# FPGA_DDR3_IO.net
KiCad netlist of a schematic drawn in Altium Designer
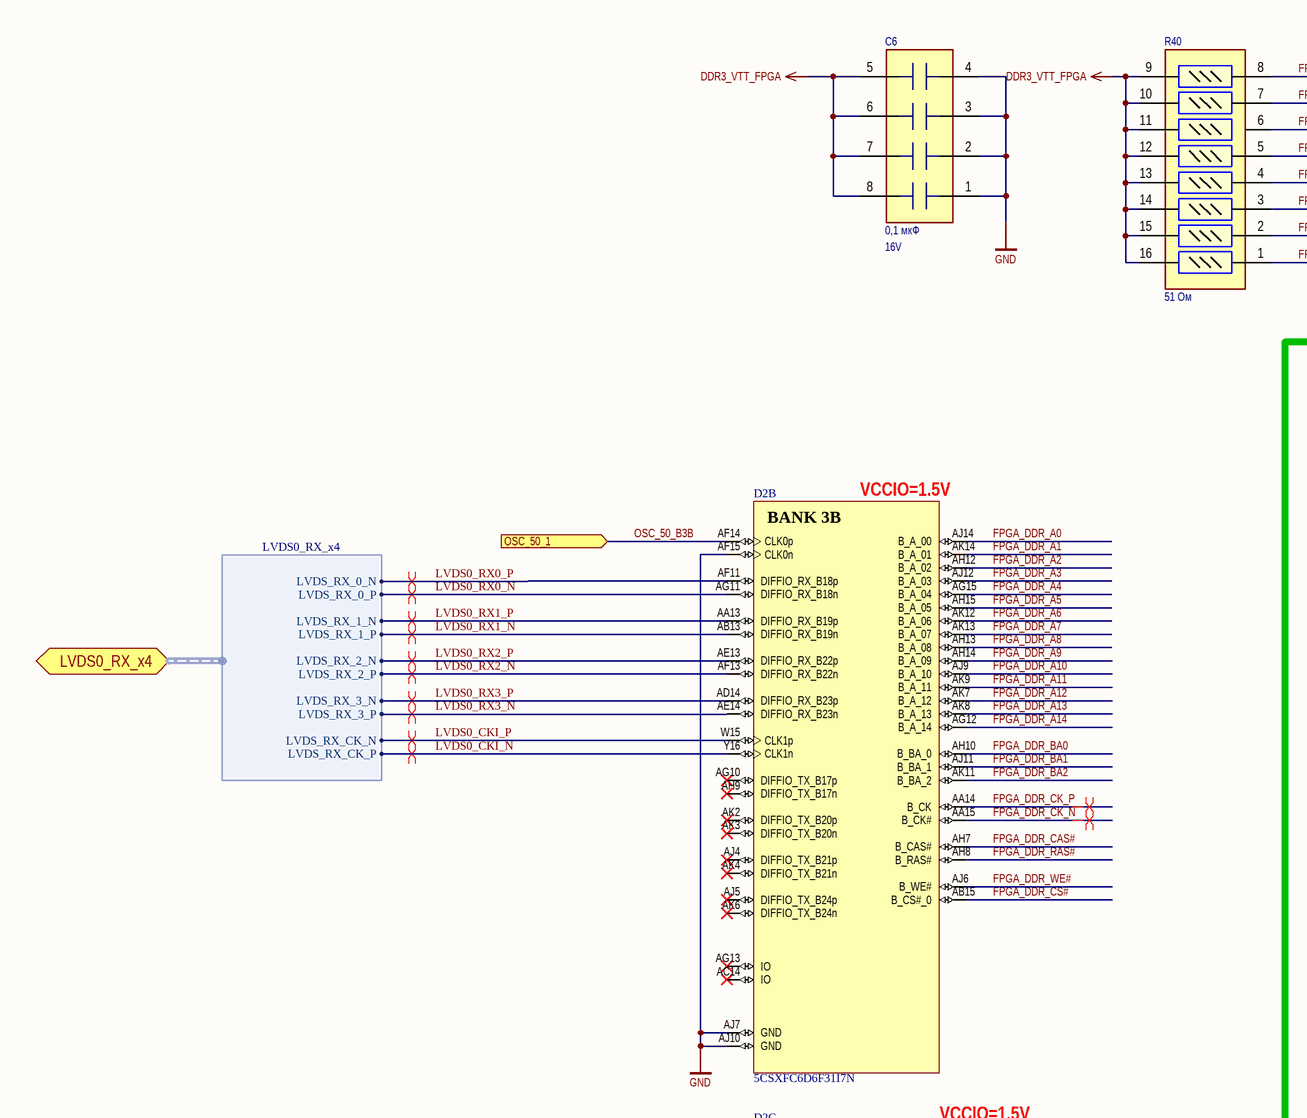
[diagram p0: FPGA_DDR3&IO.SchDoc, top left]
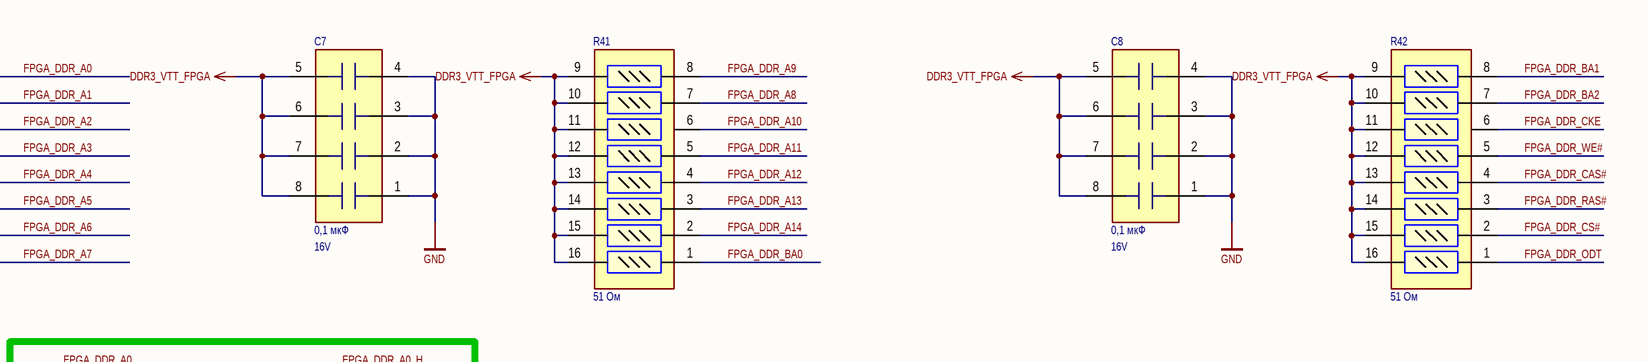
[diagram p1: FPGA_DDR3&IO.SchDoc, top right]
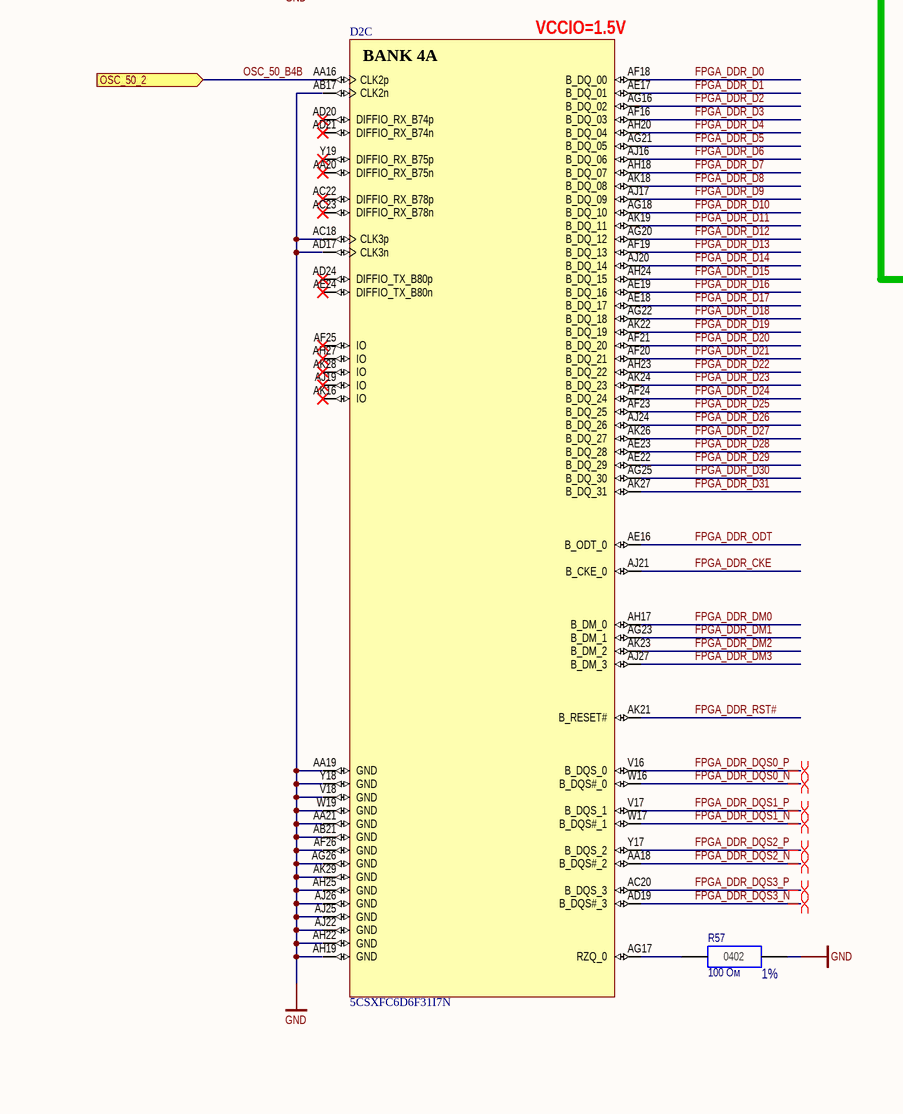
[diagram p2: FPGA_DDR3&IO.SchDoc, bottom left]
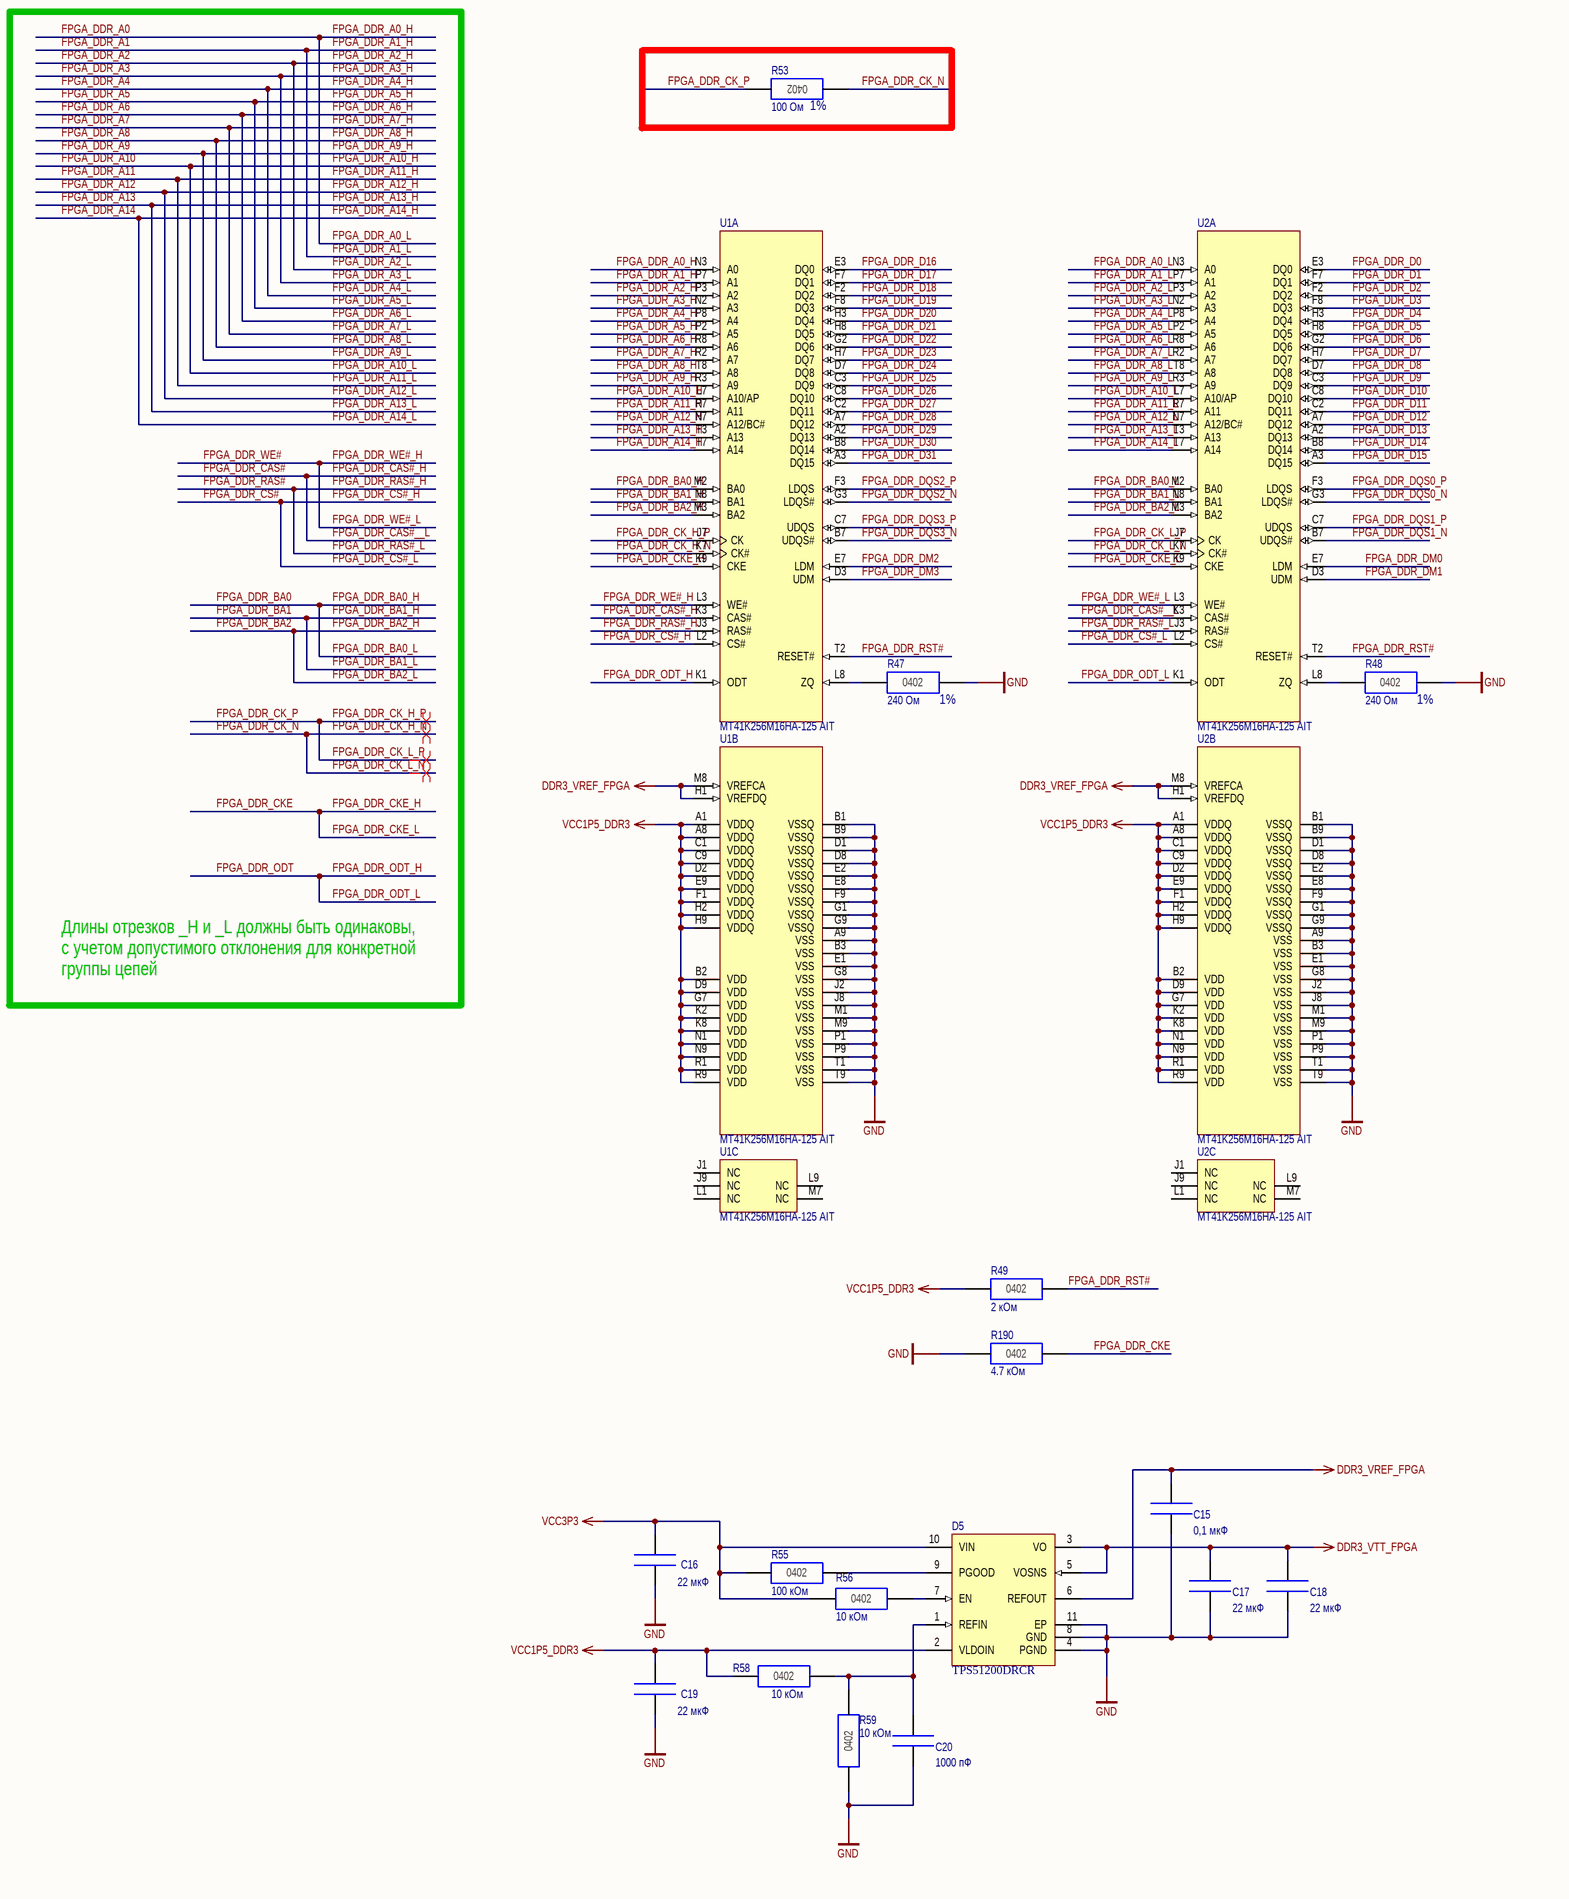
[diagram p3: FPGA_DDR3&IO.SchDoc, bottom right]

(export (version "E")
  (design (tool "Eeschema 10.0.6"))
  (components
    (comp (ref "C6")
      (value "0,1 мкФ")
      (footprint "CAF-80P319X159-8N")
      (description "Чип конденсатор керамический")
      (fields (field (name "V") "16V") (field (name "Comment") "W3A4YC104KAT2A"))
      (libsource (lib "SD_IC") (part "W3A4YC104KAT2A"))
    )
    (comp (ref "C7")
      (value "0,1 мкФ")
      (footprint "CAF-80P319X159-8N")
      (description "Чип конденсатор керамический")
      (fields (field (name "V") "16V") (field (name "Comment") "W3A4YC104KAT2A"))
      (libsource (lib "SD_IC") (part "W3A4YC104KAT2A"))
    )
    (comp (ref "C8")
      (value "0,1 мкФ")
      (footprint "CAF-80P319X159-8N")
      (description "Чип конденсатор керамический")
      (fields (field (name "V") "16V") (field (name "Comment") "W3A4YC104KAT2A"))
      (libsource (lib "SD_IC") (part "W3A4YC104KAT2A"))
    )
    (comp (ref "C15")
      (value "0,1 мкФ")
      (footprint "CC0402(1005)")
      (description "Чип конденсатор керамический")
      (fields (field (name "Comment") "CC0402-X7R-0,1 мкФ-20%-10В"))
      (libsource (lib "Чип конденсаторы") (part "CC0402-X7R-#-20%-10В"))
    )
    (comp (ref "C16")
      (value "22 мкФ")
      (footprint "CC0402(1005)")
      (description "Чип конденсатор керамический")
      (fields (field (name "Comment") "CC0402-X5R-22 мкФ-20%-6.3В"))
      (libsource (lib "Чип конденсаторы") (part "CC0402-X7R-#-20%-10В"))
    )
    (comp (ref "C17")
      (value "22 мкФ")
      (footprint "CC0402(1005)")
      (description "Чип конденсатор керамический")
      (fields (field (name "Comment") "CC0402-X5R-22 мкФ-20%-6.3В"))
      (libsource (lib "Чип конденсаторы") (part "CC0402-X7R-#-20%-10В"))
    )
    (comp (ref "C18")
      (value "22 мкФ")
      (footprint "CC0402(1005)")
      (description "Чип конденсатор керамический")
      (fields (field (name "Comment") "CC0402-X5R-22 мкФ-20%-6.3В"))
      (libsource (lib "Чип конденсаторы") (part "CC0402-X7R-#-20%-10В"))
    )
    (comp (ref "C19")
      (value "22 мкФ")
      (footprint "CC0402(1005)")
      (description "Чип конденсатор керамический")
      (fields (field (name "Comment") "CC0402-X5R-22 мкФ-20%-6.3В"))
      (libsource (lib "Чип конденсаторы") (part "CC0402-X7R-#-20%-10В"))
    )
    (comp (ref "C20")
      (value "1000 пФ")
      (footprint "CC0402(1005)")
      (description "Чип конденсатор керамический")
      (fields (field (name "Comment") "CC0402-NP01000 пФ-1%-50В"))
      (libsource (lib "Чип конденсаторы") (part "CC0402-X7R-#-20%-10В"))
    )
    (comp (ref "D2")
      (value "5CSXFC6D6F31I7N")
      (footprint "ALTR-FBGA896_A-200")
      (fields (field (name "MANUFACTURER") "Altera"))
      (libsource (lib "Altera Cyclone V_sd") (part "5CSXFC6D6F31I7N"))
    )
    (comp (ref "D5")
      (value "TPS51200DRCR")
      (footprint "TI-DRC10-2400X1650TP_V")
      (fields (field (name "MANUFACTURER") "Texas Instruments"))
      (libsource (lib "SD_IC") (part "TPS51200DRCR"))
    )
    (comp (ref "R40")
      (value "51 Ом")
      (footprint "CAT16-J8")
      (description "Набор чип резисторов")
      (fields (field (name "Comment") "YC248-JR-07-51 Ом"))
      (libsource (lib "SD_IC") (part "YC248-JR-07-#"))
    )
    (comp (ref "R41")
      (value "51 Ом")
      (footprint "CAT16-J8")
      (description "Набор чип резисторов")
      (fields (field (name "Comment") "YC248-JR-07-51 Ом"))
      (libsource (lib "SD_IC") (part "YC248-JR-07-#"))
    )
    (comp (ref "R42")
      (value "51 Ом")
      (footprint "CAT16-J8")
      (description "Набор чип резисторов")
      (fields (field (name "Comment") "YC248-JR-07-51 Ом"))
      (libsource (lib "SD_IC") (part "YC248-JR-07-#"))
    )
    (comp (ref "R47")
      (value "240 Ом")
      (footprint "CR0402(1005)")
      (description "Чип резистор")
      (fields (field (name "TOLERANCE") "1%") (field (name "Comment") "CR0402-240 Ом-±TOLERANCE"))
      (libsource (lib "Резисторы") (part "CR0402-#-±5%"))
    )
    (comp (ref "R48")
      (value "240 Ом")
      (footprint "CR0402(1005)")
      (description "Чип резистор")
      (fields (field (name "TOLERANCE") "1%") (field (name "Comment") "CR0402-240 Ом-±TOLERANCE"))
      (libsource (lib "Резисторы") (part "CR0402-#-±5%"))
    )
    (comp (ref "R49")
      (value "2 кОм")
      (footprint "CR0402(1005)")
      (description "Чип резистор")
      (fields (field (name "TOLERANCE") "5%") (field (name "Comment") "CR0402-2 кОм-±5%"))
      (libsource (lib "Резисторы") (part "CR0402-#-±5%"))
    )
    (comp (ref "R53")
      (value "100 Ом")
      (footprint "CR0402(1005)")
      (description "Чип резистор")
      (fields (field (name "TOLERANCE") "1%") (field (name "Comment") "CR0402-100 Ом-±TOLERANCE"))
      (libsource (lib "") (part "CR0402-#-±5%_2"))
    )
    (comp (ref "R55")
      (value "100 кОм")
      (footprint "CR0402(1005)")
      (description "Чип резистор")
      (fields (field (name "TOLERANCE") "5%") (field (name "Comment") "CR0402-100 кОм-±5%"))
      (libsource (lib "Резисторы") (part "CR0402-#-±5%"))
    )
    (comp (ref "R56")
      (value "10 кОм")
      (footprint "CR0402(1005)")
      (description "Чип резистор")
      (fields (field (name "TOLERANCE") "5%") (field (name "Comment") "CR0402-10 кОм-±5%"))
      (libsource (lib "Резисторы") (part "CR0402-#-±5%"))
    )
    (comp (ref "R57")
      (value "100 Ом")
      (footprint "CR0402(1005)")
      (description "Чип резистор")
      (fields (field (name "TOLERANCE") "1%") (field (name "Comment") "CR0402-100 Ом-±TOLERANCE"))
      (libsource (lib "Резисторы") (part "CR0402-#-±5%"))
    )
    (comp (ref "R58")
      (value "10 кОм")
      (footprint "CR0402(1005)")
      (description "Чип резистор")
      (fields (field (name "TOLERANCE") "5%") (field (name "Comment") "CR0402-10 кОм-±5%"))
      (libsource (lib "Резисторы") (part "CR0402-#-±5%"))
    )
    (comp (ref "R59")
      (value "10 кОм")
      (footprint "CR0402(1005)")
      (description "Чип резистор")
      (fields (field (name "TOLERANCE") "5%") (field (name "Comment") "CR0402-10 кОм-±5%"))
      (libsource (lib "") (part "CR0402-#-±5%_1"))
    )
    (comp (ref "R190")
      (value "4.7 кОм")
      (footprint "CR0402(1005)")
      (description "Чип резистор")
      (fields (field (name "TOLERANCE") "5%") (field (name "Comment") "CR0402-4.7 кОм-±5%"))
      (libsource (lib "Резисторы") (part "CR0402-#-±5%"))
    )
    (comp (ref "U1")
      (value "MT41K256M16HA-125 AIT")
      (footprint "MICT-HA-96")
      (description "4Gb DDR3-1600 SDRAM, 256Mb x 16, 1.25ns, 1.35V, -40 to 95 degC, 96-Ball FBGA, Pb-Free")
      (fields (field (name "VOLTAGE") "1.35V ") (field (name "MANUFACTURER") "Micron"))
      (libsource (lib "SD_IC") (part "MT41K256M16HA-125 AIT"))
    )
    (comp (ref "U2")
      (value "MT41K256M16HA-125 AIT")
      (footprint "MICT-HA-96")
      (description "4Gb DDR3-1600 SDRAM, 256Mb x 16, 1.25ns, 1.35V, -40 to 95 degC, 96-Ball FBGA, Pb-Free")
      (fields (field (name "VOLTAGE") "1.35V ") (field (name "MANUFACTURER") "Micron"))
      (libsource (lib "SD_IC") (part "MT41K256M16HA-125 AIT"))
    )
  )
  (nets
    (net (code "2") (name "/FPGA_DDR_A0") (class "Default")
      (node (ref "D2") (pin "AJ14") (pinfunction "B_A_00_AJ14") (pintype "bidirectional"))
      (node (ref "R40") (pin "8") (pintype "passive"))
      (node (ref "U1") (pin "N3") (pinfunction "A0_N3") (pintype "input"))
      (node (ref "U2") (pin "N3") (pinfunction "A0_N3") (pintype "input"))
    )
    (net (code "3") (name "/FPGA_DDR_A1") (class "Default")
      (node (ref "D2") (pin "AK14") (pinfunction "B_A_01_AK14") (pintype "bidirectional"))
      (node (ref "R40") (pin "7") (pintype "passive"))
      (node (ref "U1") (pin "P7") (pinfunction "A1_P7") (pintype "input"))
      (node (ref "U2") (pin "P7") (pinfunction "A1_P7") (pintype "input"))
    )
    (net (code "4") (name "/FPGA_DDR_A2") (class "Default")
      (node (ref "D2") (pin "AH12") (pinfunction "B_A_02_AH12") (pintype "bidirectional"))
      (node (ref "R40") (pin "6") (pintype "passive"))
      (node (ref "U1") (pin "P3") (pinfunction "A2_P3") (pintype "input"))
      (node (ref "U2") (pin "P3") (pinfunction "A2_P3") (pintype "input"))
    )
    (net (code "5") (name "/FPGA_DDR_A3") (class "Default")
      (node (ref "D2") (pin "AJ12") (pinfunction "B_A_03_AJ12") (pintype "bidirectional"))
      (node (ref "R40") (pin "5") (pintype "passive"))
      (node (ref "U1") (pin "N2") (pinfunction "A3_N2") (pintype "input"))
      (node (ref "U2") (pin "N2") (pinfunction "A3_N2") (pintype "input"))
    )
    (net (code "6") (name "/FPGA_DDR_A4") (class "Default")
      (node (ref "D2") (pin "AG15") (pinfunction "B_A_04_AG15") (pintype "bidirectional"))
      (node (ref "R40") (pin "4") (pintype "passive"))
      (node (ref "U1") (pin "P8") (pinfunction "A4_P8") (pintype "input"))
      (node (ref "U2") (pin "P8") (pinfunction "A4_P8") (pintype "input"))
    )
    (net (code "7") (name "/FPGA_DDR_A5") (class "Default")
      (node (ref "D2") (pin "AH15") (pinfunction "B_A_05_AH15") (pintype "bidirectional"))
      (node (ref "R40") (pin "3") (pintype "passive"))
      (node (ref "U1") (pin "P2") (pinfunction "A5_P2") (pintype "input"))
      (node (ref "U2") (pin "P2") (pinfunction "A5_P2") (pintype "input"))
    )
    (net (code "8") (name "/FPGA_DDR_A6") (class "Default")
      (node (ref "D2") (pin "AK12") (pinfunction "B_A_06_AK12") (pintype "bidirectional"))
      (node (ref "R40") (pin "2") (pintype "passive"))
      (node (ref "U1") (pin "R8") (pinfunction "A6_R8") (pintype "input"))
      (node (ref "U2") (pin "R8") (pinfunction "A6_R8") (pintype "input"))
    )
    (net (code "9") (name "/FPGA_DDR_A7") (class "Default")
      (node (ref "D2") (pin "AK13") (pinfunction "B_A_07_AK13") (pintype "bidirectional"))
      (node (ref "R40") (pin "1") (pintype "passive"))
      (node (ref "U1") (pin "R2") (pinfunction "A7_R2") (pintype "input"))
      (node (ref "U2") (pin "R2") (pinfunction "A7_R2") (pintype "input"))
    )
    (net (code "10") (name "/FPGA_DDR_A8") (class "Default")
      (node (ref "D2") (pin "AH13") (pinfunction "B_A_08_AH13") (pintype "bidirectional"))
      (node (ref "R41") (pin "7") (pintype "passive"))
      (node (ref "U1") (pin "T8") (pinfunction "A8_T8") (pintype "input"))
      (node (ref "U2") (pin "T8") (pinfunction "A8_T8") (pintype "input"))
    )
    (net (code "11") (name "/FPGA_DDR_A9") (class "Default")
      (node (ref "D2") (pin "AH14") (pinfunction "B_A_09_AH14") (pintype "bidirectional"))
      (node (ref "R41") (pin "8") (pintype "passive"))
      (node (ref "U1") (pin "R3") (pinfunction "A9_R3") (pintype "input"))
      (node (ref "U2") (pin "R3") (pinfunction "A9_R3") (pintype "input"))
    )
    (net (code "12") (name "/FPGA_DDR_A10") (class "Default")
      (node (ref "D2") (pin "AJ9") (pinfunction "B_A_10_AJ9") (pintype "bidirectional"))
      (node (ref "R41") (pin "6") (pintype "passive"))
      (node (ref "U1") (pin "L7") (pinfunction "A10/AP_L7") (pintype "input"))
      (node (ref "U2") (pin "L7") (pinfunction "A10/AP_L7") (pintype "input"))
    )
    (net (code "13") (name "/FPGA_DDR_A11") (class "Default")
      (node (ref "D2") (pin "AK9") (pinfunction "B_A_11_AK9") (pintype "bidirectional"))
      (node (ref "R41") (pin "5") (pintype "passive"))
      (node (ref "U1") (pin "R7") (pinfunction "A11_R7") (pintype "input"))
      (node (ref "U2") (pin "R7") (pinfunction "A11_R7") (pintype "input"))
    )
    (net (code "14") (name "/FPGA_DDR_A12") (class "Default")
      (node (ref "D2") (pin "AK7") (pinfunction "B_A_12_AK7") (pintype "bidirectional"))
      (node (ref "R41") (pin "4") (pintype "passive"))
      (node (ref "U1") (pin "N7") (pinfunction "A12/BC#_N7") (pintype "input"))
      (node (ref "U2") (pin "N7") (pinfunction "A12/BC#_N7") (pintype "input"))
    )
    (net (code "15") (name "/FPGA_DDR_A13") (class "Default")
      (node (ref "D2") (pin "AK8") (pinfunction "B_A_13_AK8") (pintype "bidirectional"))
      (node (ref "R41") (pin "3") (pintype "passive"))
      (node (ref "U1") (pin "T3") (pinfunction "A13_T3") (pintype "input"))
      (node (ref "U2") (pin "T3") (pinfunction "A13_T3") (pintype "input"))
    )
    (net (code "16") (name "/FPGA_DDR_A14") (class "Default")
      (node (ref "D2") (pin "AG12") (pinfunction "B_A_14_AG12") (pintype "bidirectional"))
      (node (ref "R41") (pin "2") (pintype "passive"))
      (node (ref "U1") (pin "T7") (pinfunction "A14_T7") (pintype "input"))
      (node (ref "U2") (pin "T7") (pinfunction "A14_T7") (pintype "input"))
    )
    (net (code "17") (name "/FPGA_DDR_BA0") (class "Default")
      (node (ref "D2") (pin "AH10") (pinfunction "B_BA_0_AH10") (pintype "bidirectional"))
      (node (ref "R41") (pin "1") (pintype "passive"))
      (node (ref "U1") (pin "M2") (pinfunction "BA0_M2") (pintype "input"))
      (node (ref "U2") (pin "M2") (pinfunction "BA0_M2") (pintype "input"))
    )
    (net (code "18") (name "/FPGA_DDR_BA1") (class "Default")
      (node (ref "D2") (pin "AJ11") (pinfunction "B_BA_1_AJ11") (pintype "bidirectional"))
      (node (ref "R42") (pin "8") (pintype "passive"))
      (node (ref "U1") (pin "N8") (pinfunction "BA1_N8") (pintype "input"))
      (node (ref "U2") (pin "N8") (pinfunction "BA1_N8") (pintype "input"))
    )
    (net (code "19") (name "/FPGA_DDR_BA2") (class "Default")
      (node (ref "D2") (pin "AK11") (pinfunction "B_BA_2_AK11") (pintype "bidirectional"))
      (node (ref "R42") (pin "7") (pintype "passive"))
      (node (ref "U1") (pin "M3") (pinfunction "BA2_M3") (pintype "input"))
      (node (ref "U2") (pin "M3") (pinfunction "BA2_M3") (pintype "input"))
    )
    (net (code "20") (name "/FPGA_DDR_CAS#") (class "Default")
      (node (ref "D2") (pin "AH7") (pinfunction "B_CAS#_AH7") (pintype "bidirectional"))
      (node (ref "R42") (pin "4") (pintype "passive"))
      (node (ref "U1") (pin "K3") (pinfunction "CAS#_K3") (pintype "input"))
      (node (ref "U2") (pin "K3") (pinfunction "CAS#_K3") (pintype "input"))
    )
    (net (code "21") (name "/FPGA_DDR_CKE") (class "Default")
      (node (ref "D2") (pin "AJ21") (pinfunction "B_CKE_0_AJ21") (pintype "bidirectional"))
      (node (ref "R190") (pin "2") (pinfunction "-_2") (pintype "passive"))
      (node (ref "R42") (pin "6") (pintype "passive"))
      (node (ref "U1") (pin "K9") (pinfunction "CKE_K9") (pintype "input"))
      (node (ref "U2") (pin "K9") (pinfunction "CKE_K9") (pintype "input"))
    )
    (net (code "22") (name "/FPGA_DDR_CK_H_N") (class "Default")
      (node (ref "D2") (pin "AA15") (pinfunction "B_CK#_AA15") (pintype "bidirectional"))
      (node (ref "R53") (pin "1") (pinfunction "+_1") (pintype "passive"))
      (node (ref "U1") (pin "K7") (pinfunction "CK#_K7") (pintype "input"))
      (node (ref "U2") (pin "K7") (pinfunction "CK#_K7") (pintype "input"))
    )
    (net (code "23") (name "/FPGA_DDR_CK_H_P") (class "Default")
      (node (ref "D2") (pin "AA14") (pinfunction "B_CK_AA14") (pintype "bidirectional"))
      (node (ref "R53") (pin "2") (pinfunction "-_2") (pintype "passive"))
      (node (ref "U1") (pin "J7") (pinfunction "CK_J7") (pintype "input"))
      (node (ref "U2") (pin "J7") (pinfunction "CK_J7") (pintype "input"))
    )
    (net (code "24") (name "/FPGA_DDR_CS#") (class "Default")
      (node (ref "D2") (pin "AB15") (pinfunction "B_CS#_0_AB15") (pintype "bidirectional"))
      (node (ref "R42") (pin "2") (pintype "passive"))
      (node (ref "U1") (pin "L2") (pinfunction "CS#_L2") (pintype "input"))
      (node (ref "U2") (pin "L2") (pinfunction "CS#_L2") (pintype "input"))
    )
    (net (code "25") (name "/FPGA_DDR_D0") (class "Default")
      (node (ref "D2") (pin "AF18") (pinfunction "B_DQ_00_AF18") (pintype "bidirectional"))
      (node (ref "U2") (pin "E3") (pinfunction "DQ0_E3") (pintype "bidirectional"))
    )
    (net (code "26") (name "/FPGA_DDR_D1") (class "Default")
      (node (ref "D2") (pin "AE17") (pinfunction "B_DQ_01_AE17") (pintype "bidirectional"))
      (node (ref "U2") (pin "F7") (pinfunction "DQ1_F7") (pintype "bidirectional"))
    )
    (net (code "27") (name "/FPGA_DDR_D2") (class "Default")
      (node (ref "D2") (pin "AG16") (pinfunction "B_DQ_02_AG16") (pintype "bidirectional"))
      (node (ref "U2") (pin "F2") (pinfunction "DQ2_F2") (pintype "bidirectional"))
    )
    (net (code "28") (name "/FPGA_DDR_D3") (class "Default")
      (node (ref "D2") (pin "AF16") (pinfunction "B_DQ_03_AF16") (pintype "bidirectional"))
      (node (ref "U2") (pin "F8") (pinfunction "DQ3_F8") (pintype "bidirectional"))
    )
    (net (code "29") (name "/FPGA_DDR_D4") (class "Default")
      (node (ref "D2") (pin "AH20") (pinfunction "B_DQ_04_AH20") (pintype "bidirectional"))
      (node (ref "U2") (pin "H3") (pinfunction "DQ4_H3") (pintype "bidirectional"))
    )
    (net (code "30") (name "/FPGA_DDR_D5") (class "Default")
      (node (ref "D2") (pin "AG21") (pinfunction "B_DQ_05_AG21") (pintype "bidirectional"))
      (node (ref "U2") (pin "H8") (pinfunction "DQ5_H8") (pintype "bidirectional"))
    )
    (net (code "31") (name "/FPGA_DDR_D6") (class "Default")
      (node (ref "D2") (pin "AJ16") (pinfunction "B_DQ_06_AJ16") (pintype "bidirectional"))
      (node (ref "U2") (pin "G2") (pinfunction "DQ6_G2") (pintype "bidirectional"))
    )
    (net (code "32") (name "/FPGA_DDR_D7") (class "Default")
      (node (ref "D2") (pin "AH18") (pinfunction "B_DQ_07_AH18") (pintype "bidirectional"))
      (node (ref "U2") (pin "H7") (pinfunction "DQ7_H7") (pintype "bidirectional"))
    )
    (net (code "33") (name "/FPGA_DDR_D8") (class "Default")
      (node (ref "D2") (pin "AK18") (pinfunction "B_DQ_08_AK18") (pintype "bidirectional"))
      (node (ref "U2") (pin "D7") (pinfunction "DQ8_D7") (pintype "bidirectional"))
    )
    (net (code "34") (name "/FPGA_DDR_D9") (class "Default")
      (node (ref "D2") (pin "AJ17") (pinfunction "B_DQ_09_AJ17") (pintype "bidirectional"))
      (node (ref "U2") (pin "C3") (pinfunction "DQ9_C3") (pintype "bidirectional"))
    )
    (net (code "35") (name "/FPGA_DDR_D10") (class "Default")
      (node (ref "D2") (pin "AG18") (pinfunction "B_DQ_10_AG18") (pintype "bidirectional"))
      (node (ref "U2") (pin "C8") (pinfunction "DQ10_C8") (pintype "bidirectional"))
    )
    (net (code "36") (name "/FPGA_DDR_D11") (class "Default")
      (node (ref "D2") (pin "AK19") (pinfunction "B_DQ_11_AK19") (pintype "bidirectional"))
      (node (ref "U2") (pin "C2") (pinfunction "DQ11_C2") (pintype "bidirectional"))
    )
    (net (code "37") (name "/FPGA_DDR_D12") (class "Default")
      (node (ref "D2") (pin "AG20") (pinfunction "B_DQ_12_AG20") (pintype "bidirectional"))
      (node (ref "U2") (pin "A7") (pinfunction "DQ12_A7") (pintype "bidirectional"))
    )
    (net (code "38") (name "/FPGA_DDR_D13") (class "Default")
      (node (ref "D2") (pin "AF19") (pinfunction "B_DQ_13_AF19") (pintype "bidirectional"))
      (node (ref "U2") (pin "A2") (pinfunction "DQ13_A2") (pintype "bidirectional"))
    )
    (net (code "39") (name "/FPGA_DDR_D14") (class "Default")
      (node (ref "D2") (pin "AJ20") (pinfunction "B_DQ_14_AJ20") (pintype "bidirectional"))
      (node (ref "U2") (pin "B8") (pinfunction "DQ14_B8") (pintype "bidirectional"))
    )
    (net (code "40") (name "/FPGA_DDR_D15") (class "Default")
      (node (ref "D2") (pin "AH24") (pinfunction "B_DQ_15_AH24") (pintype "bidirectional"))
      (node (ref "U2") (pin "A3") (pinfunction "DQ15_A3") (pintype "bidirectional"))
    )
    (net (code "41") (name "/FPGA_DDR_D16") (class "Default")
      (node (ref "D2") (pin "AE19") (pinfunction "B_DQ_16_AE19") (pintype "bidirectional"))
      (node (ref "U1") (pin "E3") (pinfunction "DQ0_E3") (pintype "bidirectional"))
    )
    (net (code "42") (name "/FPGA_DDR_D17") (class "Default")
      (node (ref "D2") (pin "AE18") (pinfunction "B_DQ_17_AE18") (pintype "bidirectional"))
      (node (ref "U1") (pin "F7") (pinfunction "DQ1_F7") (pintype "bidirectional"))
    )
    (net (code "43") (name "/FPGA_DDR_D18") (class "Default")
      (node (ref "D2") (pin "AG22") (pinfunction "B_DQ_18_AG22") (pintype "bidirectional"))
      (node (ref "U1") (pin "F2") (pinfunction "DQ2_F2") (pintype "bidirectional"))
    )
    (net (code "44") (name "/FPGA_DDR_D19") (class "Default")
      (node (ref "D2") (pin "AK22") (pinfunction "B_DQ_19_AK22") (pintype "bidirectional"))
      (node (ref "U1") (pin "F8") (pinfunction "DQ3_F8") (pintype "bidirectional"))
    )
    (net (code "45") (name "/FPGA_DDR_D20") (class "Default")
      (node (ref "D2") (pin "AF21") (pinfunction "B_DQ_20_AF21") (pintype "bidirectional"))
      (node (ref "U1") (pin "H3") (pinfunction "DQ4_H3") (pintype "bidirectional"))
    )
    (net (code "46") (name "/FPGA_DDR_D21") (class "Default")
      (node (ref "D2") (pin "AF20") (pinfunction "B_DQ_21_AF20") (pintype "bidirectional"))
      (node (ref "U1") (pin "H8") (pinfunction "DQ5_H8") (pintype "bidirectional"))
    )
    (net (code "47") (name "/FPGA_DDR_D22") (class "Default")
      (node (ref "D2") (pin "AH23") (pinfunction "B_DQ_22_AH23") (pintype "bidirectional"))
      (node (ref "U1") (pin "G2") (pinfunction "DQ6_G2") (pintype "bidirectional"))
    )
    (net (code "48") (name "/FPGA_DDR_D23") (class "Default")
      (node (ref "D2") (pin "AK24") (pinfunction "B_DQ_23_AK24") (pintype "bidirectional"))
      (node (ref "U1") (pin "H7") (pinfunction "DQ7_H7") (pintype "bidirectional"))
    )
    (net (code "49") (name "/FPGA_DDR_D24") (class "Default")
      (node (ref "D2") (pin "AF24") (pinfunction "B_DQ_24_AF24") (pintype "bidirectional"))
      (node (ref "U1") (pin "D7") (pinfunction "DQ8_D7") (pintype "bidirectional"))
    )
    (net (code "50") (name "/FPGA_DDR_D25") (class "Default")
      (node (ref "D2") (pin "AF23") (pinfunction "B_DQ_25_AF23") (pintype "bidirectional"))
      (node (ref "U1") (pin "C3") (pinfunction "DQ9_C3") (pintype "bidirectional"))
    )
    (net (code "51") (name "/FPGA_DDR_D26") (class "Default")
      (node (ref "D2") (pin "AJ24") (pinfunction "B_DQ_26_AJ24") (pintype "bidirectional"))
      (node (ref "U1") (pin "C8") (pinfunction "DQ10_C8") (pintype "bidirectional"))
    )
    (net (code "52") (name "/FPGA_DDR_D27") (class "Default")
      (node (ref "D2") (pin "AK26") (pinfunction "B_DQ_27_AK26") (pintype "bidirectional"))
      (node (ref "U1") (pin "C2") (pinfunction "DQ11_C2") (pintype "bidirectional"))
    )
    (net (code "53") (name "/FPGA_DDR_D28") (class "Default")
      (node (ref "D2") (pin "AE23") (pinfunction "B_DQ_28_AE23") (pintype "bidirectional"))
      (node (ref "U1") (pin "A7") (pinfunction "DQ12_A7") (pintype "bidirectional"))
    )
    (net (code "54") (name "/FPGA_DDR_D29") (class "Default")
      (node (ref "D2") (pin "AE22") (pinfunction "B_DQ_29_AE22") (pintype "bidirectional"))
      (node (ref "U1") (pin "A2") (pinfunction "DQ13_A2") (pintype "bidirectional"))
    )
    (net (code "55") (name "/FPGA_DDR_D30") (class "Default")
      (node (ref "D2") (pin "AG25") (pinfunction "B_DQ_30_AG25") (pintype "bidirectional"))
      (node (ref "U1") (pin "B8") (pinfunction "DQ14_B8") (pintype "bidirectional"))
    )
    (net (code "56") (name "/FPGA_DDR_D31") (class "Default")
      (node (ref "D2") (pin "AK27") (pinfunction "B_DQ_31_AK27") (pintype "bidirectional"))
      (node (ref "U1") (pin "A3") (pinfunction "DQ15_A3") (pintype "bidirectional"))
    )
    (net (code "57") (name "/FPGA_DDR_DM0") (class "Default")
      (node (ref "D2") (pin "AH17") (pinfunction "B_DM_0_AH17") (pintype "bidirectional"))
      (node (ref "U2") (pin "E7") (pinfunction "LDM_E7") (pintype "input"))
    )
    (net (code "58") (name "/FPGA_DDR_DM1") (class "Default")
      (node (ref "D2") (pin "AG23") (pinfunction "B_DM_1_AG23") (pintype "bidirectional"))
      (node (ref "U2") (pin "D3") (pinfunction "UDM_D3") (pintype "input"))
    )
    (net (code "59") (name "/FPGA_DDR_DM2") (class "Default")
      (node (ref "D2") (pin "AK23") (pinfunction "B_DM_2_AK23") (pintype "bidirectional"))
      (node (ref "U1") (pin "E7") (pinfunction "LDM_E7") (pintype "input"))
    )
    (net (code "60") (name "/FPGA_DDR_DM3") (class "Default")
      (node (ref "D2") (pin "AJ27") (pinfunction "B_DM_3_AJ27") (pintype "bidirectional"))
      (node (ref "U1") (pin "D3") (pinfunction "UDM_D3") (pintype "input"))
    )
    (net (code "61") (name "/FPGA_DDR_DQS0_N") (class "Default")
      (node (ref "D2") (pin "W16") (pinfunction "B_DQS#_0_W16") (pintype "bidirectional"))
      (node (ref "U2") (pin "G3") (pinfunction "LDQS#_G3") (pintype "bidirectional"))
    )
    (net (code "62") (name "/FPGA_DDR_DQS0_P") (class "Default")
      (node (ref "D2") (pin "V16") (pinfunction "B_DQS_0_V16") (pintype "bidirectional"))
      (node (ref "U2") (pin "F3") (pinfunction "LDQS_F3") (pintype "bidirectional"))
    )
    (net (code "63") (name "/FPGA_DDR_DQS1_N") (class "Default")
      (node (ref "D2") (pin "W17") (pinfunction "B_DQS#_1_W17") (pintype "bidirectional"))
      (node (ref "U2") (pin "B7") (pinfunction "UDQS#_B7") (pintype "bidirectional"))
    )
    (net (code "64") (name "/FPGA_DDR_DQS1_P") (class "Default")
      (node (ref "D2") (pin "V17") (pinfunction "B_DQS_1_V17") (pintype "bidirectional"))
      (node (ref "U2") (pin "C7") (pinfunction "UDQS_C7") (pintype "bidirectional"))
    )
    (net (code "65") (name "/FPGA_DDR_DQS2_N") (class "Default")
      (node (ref "D2") (pin "AA18") (pinfunction "B_DQS#_2_AA18") (pintype "bidirectional"))
      (node (ref "U1") (pin "G3") (pinfunction "LDQS#_G3") (pintype "bidirectional"))
    )
    (net (code "66") (name "/FPGA_DDR_DQS2_P") (class "Default")
      (node (ref "D2") (pin "Y17") (pinfunction "B_DQS_2_Y17") (pintype "bidirectional"))
      (node (ref "U1") (pin "F3") (pinfunction "LDQS_F3") (pintype "bidirectional"))
    )
    (net (code "67") (name "/FPGA_DDR_DQS3_N") (class "Default")
      (node (ref "D2") (pin "AD19") (pinfunction "B_DQS#_3_AD19") (pintype "bidirectional"))
      (node (ref "U1") (pin "B7") (pinfunction "UDQS#_B7") (pintype "bidirectional"))
    )
    (net (code "68") (name "/FPGA_DDR_DQS3_P") (class "Default")
      (node (ref "D2") (pin "AC20") (pinfunction "B_DQS_3_AC20") (pintype "bidirectional"))
      (node (ref "U1") (pin "C7") (pinfunction "UDQS_C7") (pintype "bidirectional"))
    )
    (net (code "69") (name "/FPGA_DDR_ODT") (class "Default")
      (node (ref "D2") (pin "AE16") (pinfunction "B_ODT_0_AE16") (pintype "bidirectional"))
      (node (ref "R42") (pin "1") (pintype "passive"))
      (node (ref "U1") (pin "K1") (pinfunction "ODT_K1") (pintype "input"))
      (node (ref "U2") (pin "K1") (pinfunction "ODT_K1") (pintype "input"))
    )
    (net (code "70") (name "/FPGA_DDR_RAS#") (class "Default")
      (node (ref "D2") (pin "AH8") (pinfunction "B_RAS#_AH8") (pintype "bidirectional"))
      (node (ref "R42") (pin "3") (pintype "passive"))
      (node (ref "U1") (pin "J3") (pinfunction "RAS#_J3") (pintype "input"))
      (node (ref "U2") (pin "J3") (pinfunction "RAS#_J3") (pintype "input"))
    )
    (net (code "71") (name "/FPGA_DDR_RST#") (class "Default")
      (node (ref "D2") (pin "AK21") (pinfunction "B_RESET#_AK21") (pintype "bidirectional"))
      (node (ref "R49") (pin "2") (pinfunction "-_2") (pintype "passive"))
      (node (ref "U1") (pin "T2") (pinfunction "RESET#_T2") (pintype "input"))
      (node (ref "U2") (pin "T2") (pinfunction "RESET#_T2") (pintype "input"))
    )
    (net (code "72") (name "/FPGA_DDR_WE#") (class "Default")
      (node (ref "D2") (pin "AJ6") (pinfunction "B_WE#_AJ6") (pintype "bidirectional"))
      (node (ref "R42") (pin "5") (pintype "passive"))
      (node (ref "U1") (pin "L3") (pinfunction "WE#_L3") (pintype "input"))
      (node (ref "U2") (pin "L3") (pinfunction "WE#_L3") (pintype "input"))
    )
    (net (code "74") (name "/LVDS0_CKI_P") (class "Default")
      (node (ref "D2") (pin "W15") (pinfunction "CLK1p_W15") (pintype "bidirectional"))
    )
    (net (code "76") (name "/LVDS0_RX0_P") (class "Default")
      (node (ref "D2") (pin "AF11") (pinfunction "DIFFIO_RX_B18p_AF11") (pintype "bidirectional"))
    )
    (net (code "77") (name "/LVDS0_RX1_N") (class "Default")
      (node (ref "D2") (pin "AB13") (pinfunction "DIFFIO_RX_B19n_AB13") (pintype "bidirectional"))
    )
    (net (code "78") (name "/LVDS0_RX1_P") (class "Default")
      (node (ref "D2") (pin "AA13") (pinfunction "DIFFIO_RX_B19p_AA13") (pintype "bidirectional"))
    )
    (net (code "79") (name "/LVDS0_RX2_N") (class "Default")
      (node (ref "D2") (pin "AF13") (pinfunction "DIFFIO_RX_B22n_AF13") (pintype "bidirectional"))
    )
    (net (code "80") (name "/LVDS0_RX2_P") (class "Default")
      (node (ref "D2") (pin "AE13") (pinfunction "DIFFIO_RX_B22p_AE13") (pintype "bidirectional"))
    )
    (net (code "82") (name "/LVDS0_RX3_N") (class "Default")
      (node (ref "D2") (pin "AE14") (pinfunction "DIFFIO_RX_B23n_AE14") (pintype "bidirectional"))
    )
    (net (code "83") (name "/LVDS0_RX3_P") (class "Default")
      (node (ref "D2") (pin "AD14") (pinfunction "DIFFIO_RX_B23p_AD14") (pintype "bidirectional"))
    )
    (net (code "84") (name "/OSC_50_B3B") (class "Default")
      (node (ref "D2") (pin "AF14") (pinfunction "CLK0p_AF14") (pintype "bidirectional"))
    )
    (net (code "86") (name "/OSC_50_B4B") (class "Default")
      (node (ref "D2") (pin "AA16") (pinfunction "CLK2p_AA16") (pintype "bidirectional"))
    )
    (net (code "87") (name "DDR3_VREF_FPGA") (class "Default")
      (node (ref "C15") (pin "1") (pinfunction "+_1") (pintype "passive"))
      (node (ref "D5") (pin "6") (pinfunction "REFOUT_6") (pintype "power_in"))
      (node (ref "U1") (pin "H1") (pinfunction "VREFDQ_H1") (pintype "input"))
      (node (ref "U1") (pin "M8") (pinfunction "VREFCA_M8") (pintype "input"))
      (node (ref "U2") (pin "H1") (pinfunction "VREFDQ_H1") (pintype "input"))
      (node (ref "U2") (pin "M8") (pinfunction "VREFCA_M8") (pintype "input"))
    )
    (net (code "88") (name "DDR3_VTT_FPGA") (class "Default")
      (node (ref "C17") (pin "1") (pinfunction "+_1") (pintype "passive"))
      (node (ref "C18") (pin "1") (pinfunction "+_1") (pintype "passive"))
      (node (ref "C6") (pin "5") (pintype "passive"))
      (node (ref "C6") (pin "6") (pintype "passive"))
      (node (ref "C6") (pin "7") (pintype "passive"))
      (node (ref "C6") (pin "8") (pintype "passive"))
      (node (ref "C7") (pin "5") (pintype "passive"))
      (node (ref "C7") (pin "6") (pintype "passive"))
      (node (ref "C7") (pin "7") (pintype "passive"))
      (node (ref "C7") (pin "8") (pintype "passive"))
      (node (ref "C8") (pin "5") (pintype "passive"))
      (node (ref "C8") (pin "6") (pintype "passive"))
      (node (ref "C8") (pin "7") (pintype "passive"))
      (node (ref "C8") (pin "8") (pintype "passive"))
      (node (ref "D5") (pin "3") (pinfunction "VO_3") (pintype "power_in"))
      (node (ref "D5") (pin "5") (pinfunction "VOSNS_5") (pintype "input"))
      (node (ref "R40") (pin "10") (pintype "passive"))
      (node (ref "R40") (pin "11") (pintype "passive"))
      (node (ref "R40") (pin "12") (pintype "passive"))
      (node (ref "R40") (pin "13") (pintype "passive"))
      (node (ref "R40") (pin "14") (pintype "passive"))
      (node (ref "R40") (pin "15") (pintype "passive"))
      (node (ref "R40") (pin "16") (pintype "passive"))
      (node (ref "R40") (pin "9") (pintype "passive"))
      (node (ref "R41") (pin "10") (pintype "passive"))
      (node (ref "R41") (pin "11") (pintype "passive"))
      (node (ref "R41") (pin "12") (pintype "passive"))
      (node (ref "R41") (pin "13") (pintype "passive"))
      (node (ref "R41") (pin "14") (pintype "passive"))
      (node (ref "R41") (pin "15") (pintype "passive"))
      (node (ref "R41") (pin "16") (pintype "passive"))
      (node (ref "R41") (pin "9") (pintype "passive"))
      (node (ref "R42") (pin "10") (pintype "passive"))
      (node (ref "R42") (pin "11") (pintype "passive"))
      (node (ref "R42") (pin "12") (pintype "passive"))
      (node (ref "R42") (pin "13") (pintype "passive"))
      (node (ref "R42") (pin "14") (pintype "passive"))
      (node (ref "R42") (pin "15") (pintype "passive"))
      (node (ref "R42") (pin "16") (pintype "passive"))
      (node (ref "R42") (pin "9") (pintype "passive"))
    )
    (net (code "89") (name "GND") (class "Default")
      (node (ref "C15") (pin "2") (pinfunction "-_2") (pintype "passive"))
      (node (ref "C16") (pin "2") (pinfunction "-_2") (pintype "passive"))
      (node (ref "C17") (pin "2") (pinfunction "-_2") (pintype "passive"))
      (node (ref "C18") (pin "2") (pinfunction "-_2") (pintype "passive"))
      (node (ref "C19") (pin "2") (pinfunction "-_2") (pintype "passive"))
      (node (ref "C20") (pin "2") (pinfunction "-_2") (pintype "passive"))
      (node (ref "C6") (pin "1") (pintype "passive"))
      (node (ref "C6") (pin "2") (pintype "passive"))
      (node (ref "C6") (pin "3") (pintype "passive"))
      (node (ref "C6") (pin "4") (pintype "passive"))
      (node (ref "C7") (pin "1") (pintype "passive"))
      (node (ref "C7") (pin "2") (pintype "passive"))
      (node (ref "C7") (pin "3") (pintype "passive"))
      (node (ref "C7") (pin "4") (pintype "passive"))
      (node (ref "C8") (pin "1") (pintype "passive"))
      (node (ref "C8") (pin "2") (pintype "passive"))
      (node (ref "C8") (pin "3") (pintype "passive"))
      (node (ref "C8") (pin "4") (pintype "passive"))
      (node (ref "D2") (pin "AF15") (pinfunction "CLK0n_AF15") (pintype "bidirectional"))
      (node (ref "D2") (pin "AJ10") (pinfunction "GND_AJ10") (pintype "bidirectional"))
      (node (ref "D2") (pin "AJ22") (pinfunction "GND_AJ22") (pintype "bidirectional"))
      (node (ref "D2") (pin "AJ7") (pinfunction "GND_AJ7") (pintype "bidirectional"))
      (node (ref "D5") (pin "11") (pinfunction "EP_11") (pintype "power_in"))
      (node (ref "D5") (pin "4") (pinfunction "PGND_4") (pintype "power_in"))
      (node (ref "D5") (pin "8") (pinfunction "GND_8") (pintype "power_in"))
      (node (ref "R190") (pin "1") (pinfunction "+_1") (pintype "passive"))
      (node (ref "R47") (pin "2") (pinfunction "-_2") (pintype "passive"))
      (node (ref "R48") (pin "2") (pinfunction "-_2") (pintype "passive"))
      (node (ref "R57") (pin "2") (pinfunction "-_2") (pintype "passive"))
      (node (ref "R59") (pin "1") (pinfunction "+_1") (pintype "passive"))
      (node (ref "U1") (pin "A9") (pinfunction "VSS_A9") (pintype "power_in"))
      (node (ref "U1") (pin "B1") (pinfunction "VSSQ_B1") (pintype "power_in"))
      (node (ref "U1") (pin "B3") (pinfunction "VSS_B3") (pintype "power_in"))
      (node (ref "U1") (pin "B9") (pinfunction "VSSQ_B9") (pintype "power_in"))
      (node (ref "U1") (pin "D1") (pinfunction "VSSQ_D1") (pintype "power_in"))
      (node (ref "U1") (pin "D8") (pinfunction "VSSQ_D8") (pintype "power_in"))
      (node (ref "U1") (pin "E1") (pinfunction "VSS_E1") (pintype "power_in"))
      (node (ref "U1") (pin "E2") (pinfunction "VSSQ_E2") (pintype "power_in"))
      (node (ref "U1") (pin "E8") (pinfunction "VSSQ_E8") (pintype "power_in"))
      (node (ref "U1") (pin "F9") (pinfunction "VSSQ_F9") (pintype "power_in"))
      (node (ref "U1") (pin "G1") (pinfunction "VSSQ_G1") (pintype "power_in"))
      (node (ref "U1") (pin "G8") (pinfunction "VSS_G8") (pintype "power_in"))
      (node (ref "U1") (pin "G9") (pinfunction "VSSQ_G9") (pintype "power_in"))
      (node (ref "U1") (pin "J2") (pinfunction "VSS_J2") (pintype "power_in"))
      (node (ref "U1") (pin "J8") (pinfunction "VSS_J8") (pintype "power_in"))
      (node (ref "U1") (pin "M1") (pinfunction "VSS_M1") (pintype "power_in"))
      (node (ref "U1") (pin "M9") (pinfunction "VSS_M9") (pintype "power_in"))
      (node (ref "U1") (pin "P1") (pinfunction "VSS_P1") (pintype "power_in"))
      (node (ref "U1") (pin "P9") (pinfunction "VSS_P9") (pintype "power_in"))
      (node (ref "U1") (pin "T1") (pinfunction "VSS_T1") (pintype "power_in"))
      (node (ref "U1") (pin "T9") (pinfunction "VSS_T9") (pintype "power_in"))
      (node (ref "U2") (pin "A9") (pinfunction "VSS_A9") (pintype "power_in"))
      (node (ref "U2") (pin "B1") (pinfunction "VSSQ_B1") (pintype "power_in"))
      (node (ref "U2") (pin "B3") (pinfunction "VSS_B3") (pintype "power_in"))
      (node (ref "U2") (pin "B9") (pinfunction "VSSQ_B9") (pintype "power_in"))
      (node (ref "U2") (pin "D1") (pinfunction "VSSQ_D1") (pintype "power_in"))
      (node (ref "U2") (pin "D8") (pinfunction "VSSQ_D8") (pintype "power_in"))
      (node (ref "U2") (pin "E1") (pinfunction "VSS_E1") (pintype "power_in"))
      (node (ref "U2") (pin "E2") (pinfunction "VSSQ_E2") (pintype "power_in"))
      (node (ref "U2") (pin "E8") (pinfunction "VSSQ_E8") (pintype "power_in"))
      (node (ref "U2") (pin "F9") (pinfunction "VSSQ_F9") (pintype "power_in"))
      (node (ref "U2") (pin "G1") (pinfunction "VSSQ_G1") (pintype "power_in"))
      (node (ref "U2") (pin "G8") (pinfunction "VSS_G8") (pintype "power_in"))
      (node (ref "U2") (pin "G9") (pinfunction "VSSQ_G9") (pintype "power_in"))
      (node (ref "U2") (pin "J2") (pinfunction "VSS_J2") (pintype "power_in"))
      (node (ref "U2") (pin "J8") (pinfunction "VSS_J8") (pintype "power_in"))
      (node (ref "U2") (pin "M1") (pinfunction "VSS_M1") (pintype "power_in"))
      (node (ref "U2") (pin "M9") (pinfunction "VSS_M9") (pintype "power_in"))
      (node (ref "U2") (pin "P1") (pinfunction "VSS_P1") (pintype "power_in"))
      (node (ref "U2") (pin "P9") (pinfunction "VSS_P9") (pintype "power_in"))
      (node (ref "U2") (pin "T1") (pinfunction "VSS_T1") (pintype "power_in"))
      (node (ref "U2") (pin "T9") (pinfunction "VSS_T9") (pintype "power_in"))
    )
    (net (code "90") (name "Net-(C20-+)") (class "Default")
      (node (ref "C20") (pin "1") (pinfunction "+_1") (pintype "passive"))
      (node (ref "D5") (pin "1") (pinfunction "REFIN_1") (pintype "input"))
      (node (ref "R58") (pin "2") (pinfunction "-_2") (pintype "passive"))
      (node (ref "R59") (pin "2") (pinfunction "-_2") (pintype "passive"))
    )
    (net (code "91") (name "Net-(D2C-RZQ_0)") (class "Default")
      (node (ref "D2") (pin "AG17") (pinfunction "RZQ_0_AG17") (pintype "bidirectional"))
      (node (ref "R57") (pin "1") (pinfunction "+_1") (pintype "passive"))
    )
    (net (code "92") (name "Net-(D5-EN)") (class "Default")
      (node (ref "D5") (pin "7") (pinfunction "EN_7") (pintype "input"))
      (node (ref "R56") (pin "2") (pinfunction "-_2") (pintype "passive"))
    )
    (net (code "93") (name "Net-(D5-PGOOD)") (class "Default")
      (node (ref "D5") (pin "9") (pinfunction "PGOOD_9") (pintype "open_collector"))
      (node (ref "R55") (pin "2") (pinfunction "-_2") (pintype "passive"))
    )
    (net (code "94") (name "Net-(R47-+)") (class "Default")
      (node (ref "R47") (pin "1") (pinfunction "+_1") (pintype "passive"))
      (node (ref "U1") (pin "L8") (pinfunction "ZQ_L8") (pintype "input"))
    )
    (net (code "95") (name "Net-(R48-+)") (class "Default")
      (node (ref "R48") (pin "1") (pinfunction "+_1") (pintype "passive"))
      (node (ref "U2") (pin "L8") (pinfunction "ZQ_L8") (pintype "input"))
    )
    (net (code "96") (name "VCC1P5_DDR3") (class "Default")
      (node (ref "C19") (pin "1") (pinfunction "+_1") (pintype "passive"))
      (node (ref "D5") (pin "2") (pinfunction "VLDOIN_2") (pintype "power_in"))
      (node (ref "R49") (pin "1") (pinfunction "+_1") (pintype "passive"))
      (node (ref "R58") (pin "1") (pinfunction "+_1") (pintype "passive"))
      (node (ref "U1") (pin "A1") (pinfunction "VDDQ_A1") (pintype "power_in"))
      (node (ref "U1") (pin "A8") (pinfunction "VDDQ_A8") (pintype "power_in"))
      (node (ref "U1") (pin "B2") (pinfunction "VDD_B2") (pintype "power_in"))
      (node (ref "U1") (pin "C1") (pinfunction "VDDQ_C1") (pintype "power_in"))
      (node (ref "U1") (pin "C9") (pinfunction "VDDQ_C9") (pintype "power_in"))
      (node (ref "U1") (pin "D2") (pinfunction "VDDQ_D2") (pintype "power_in"))
      (node (ref "U1") (pin "D9") (pinfunction "VDD_D9") (pintype "power_in"))
      (node (ref "U1") (pin "E9") (pinfunction "VDDQ_E9") (pintype "power_in"))
      (node (ref "U1") (pin "F1") (pinfunction "VDDQ_F1") (pintype "power_in"))
      (node (ref "U1") (pin "G7") (pinfunction "VDD_G7") (pintype "power_in"))
      (node (ref "U1") (pin "H2") (pinfunction "VDDQ_H2") (pintype "power_in"))
      (node (ref "U1") (pin "H9") (pinfunction "VDDQ_H9") (pintype "power_in"))
      (node (ref "U1") (pin "K2") (pinfunction "VDD_K2") (pintype "power_in"))
      (node (ref "U1") (pin "K8") (pinfunction "VDD_K8") (pintype "power_in"))
      (node (ref "U1") (pin "N1") (pinfunction "VDD_N1") (pintype "power_in"))
      (node (ref "U1") (pin "N9") (pinfunction "VDD_N9") (pintype "power_in"))
      (node (ref "U1") (pin "R1") (pinfunction "VDD_R1") (pintype "power_in"))
      (node (ref "U1") (pin "R9") (pinfunction "VDD_R9") (pintype "power_in"))
      (node (ref "U2") (pin "A1") (pinfunction "VDDQ_A1") (pintype "power_in"))
      (node (ref "U2") (pin "A8") (pinfunction "VDDQ_A8") (pintype "power_in"))
      (node (ref "U2") (pin "B2") (pinfunction "VDD_B2") (pintype "power_in"))
      (node (ref "U2") (pin "C1") (pinfunction "VDDQ_C1") (pintype "power_in"))
      (node (ref "U2") (pin "C9") (pinfunction "VDDQ_C9") (pintype "power_in"))
      (node (ref "U2") (pin "D2") (pinfunction "VDDQ_D2") (pintype "power_in"))
      (node (ref "U2") (pin "D9") (pinfunction "VDD_D9") (pintype "power_in"))
      (node (ref "U2") (pin "E9") (pinfunction "VDDQ_E9") (pintype "power_in"))
      (node (ref "U2") (pin "F1") (pinfunction "VDDQ_F1") (pintype "power_in"))
      (node (ref "U2") (pin "G7") (pinfunction "VDD_G7") (pintype "power_in"))
      (node (ref "U2") (pin "H2") (pinfunction "VDDQ_H2") (pintype "power_in"))
      (node (ref "U2") (pin "H9") (pinfunction "VDDQ_H9") (pintype "power_in"))
      (node (ref "U2") (pin "K2") (pinfunction "VDD_K2") (pintype "power_in"))
      (node (ref "U2") (pin "K8") (pinfunction "VDD_K8") (pintype "power_in"))
      (node (ref "U2") (pin "N1") (pinfunction "VDD_N1") (pintype "power_in"))
      (node (ref "U2") (pin "N9") (pinfunction "VDD_N9") (pintype "power_in"))
      (node (ref "U2") (pin "R1") (pinfunction "VDD_R1") (pintype "power_in"))
      (node (ref "U2") (pin "R9") (pinfunction "VDD_R9") (pintype "power_in"))
    )
    (net (code "97") (name "VCC3P3") (class "Default")
      (node (ref "C16") (pin "1") (pinfunction "+_1") (pintype "passive"))
      (node (ref "D5") (pin "10") (pinfunction "VIN_10") (pintype "power_in"))
      (node (ref "R55") (pin "1") (pinfunction "+_1") (pintype "passive"))
      (node (ref "R56") (pin "1") (pinfunction "+_1") (pintype "passive"))
    )
    (net (code "98") (name "unconnected-(D2B-CLK1n-PadY16)") (class "Default")
      (node (ref "D2") (pin "Y16") (pinfunction "CLK1n_Y16") (pintype "bidirectional"))
    )
    (net (code "99") (name "unconnected-(D2B-DIFFIO_RX_B18n-PadAG11)") (class "Default")
      (node (ref "D2") (pin "AG11") (pinfunction "DIFFIO_RX_B18n_AG11") (pintype "bidirectional"))
    )
    (net (code "100") (name "unconnected-(D2B-DIFFIO_TX_B17n-PadAH9)") (class "Default")
      (node (ref "D2") (pin "AH9") (pinfunction "DIFFIO_TX_B17n_AH9") (pintype "bidirectional+no_connect"))
    )
    (net (code "101") (name "unconnected-(D2B-DIFFIO_TX_B17p-PadAG10)") (class "Default")
      (node (ref "D2") (pin "AG10") (pinfunction "DIFFIO_TX_B17p_AG10") (pintype "bidirectional+no_connect"))
    )
    (net (code "102") (name "unconnected-(D2B-DIFFIO_TX_B20n-PadAK3)") (class "Default")
      (node (ref "D2") (pin "AK3") (pinfunction "DIFFIO_TX_B20n_AK3") (pintype "bidirectional+no_connect"))
    )
    (net (code "103") (name "unconnected-(D2B-DIFFIO_TX_B20p-PadAK2)") (class "Default")
      (node (ref "D2") (pin "AK2") (pinfunction "DIFFIO_TX_B20p_AK2") (pintype "bidirectional+no_connect"))
    )
    (net (code "104") (name "unconnected-(D2B-DIFFIO_TX_B21n-PadAK4)") (class "Default")
      (node (ref "D2") (pin "AK4") (pinfunction "DIFFIO_TX_B21n_AK4") (pintype "bidirectional+no_connect"))
    )
    (net (code "105") (name "unconnected-(D2B-DIFFIO_TX_B21p-PadAJ4)") (class "Default")
      (node (ref "D2") (pin "AJ4") (pinfunction "DIFFIO_TX_B21p_AJ4") (pintype "bidirectional+no_connect"))
    )
    (net (code "106") (name "unconnected-(D2B-DIFFIO_TX_B24n-PadAK6)") (class "Default")
      (node (ref "D2") (pin "AK6") (pinfunction "DIFFIO_TX_B24n_AK6") (pintype "bidirectional+no_connect"))
    )
    (net (code "107") (name "unconnected-(D2B-DIFFIO_TX_B24p-PadAJ5)") (class "Default")
      (node (ref "D2") (pin "AJ5") (pinfunction "DIFFIO_TX_B24p_AJ5") (pintype "bidirectional+no_connect"))
    )
    (net (code "108") (name "unconnected-(D2B-IO-PadAC14)") (class "Default")
      (node (ref "D2") (pin "AC14") (pinfunction "IO_AC14") (pintype "bidirectional+no_connect"))
    )
    (net (code "109") (name "unconnected-(D2B-IO-PadAG13)") (class "Default")
      (node (ref "D2") (pin "AG13") (pinfunction "IO_AG13") (pintype "bidirectional+no_connect"))
    )
    (net (code "110") (name "unconnected-(D2C-CLK2n-PadAB17)") (class "Default")
      (node (ref "D2") (pin "AB17") (pinfunction "CLK2n_AB17") (pintype "bidirectional"))
    )
    (net (code "111") (name "unconnected-(D2C-CLK3n-PadAD17)") (class "Default")
      (node (ref "D2") (pin "AD17") (pinfunction "CLK3n_AD17") (pintype "bidirectional"))
    )
    (net (code "112") (name "unconnected-(D2C-CLK3p-PadAC18)") (class "Default")
      (node (ref "D2") (pin "AC18") (pinfunction "CLK3p_AC18") (pintype "bidirectional"))
    )
    (net (code "113") (name "unconnected-(D2C-DIFFIO_RX_B74n-PadAD21)") (class "Default")
      (node (ref "D2") (pin "AD21") (pinfunction "DIFFIO_RX_B74n_AD21") (pintype "bidirectional+no_connect"))
    )
    (net (code "114") (name "unconnected-(D2C-DIFFIO_RX_B74p-PadAD20)") (class "Default")
      (node (ref "D2") (pin "AD20") (pinfunction "DIFFIO_RX_B74p_AD20") (pintype "bidirectional+no_connect"))
    )
    (net (code "115") (name "unconnected-(D2C-DIFFIO_RX_B75n-PadAA20)") (class "Default")
      (node (ref "D2") (pin "AA20") (pinfunction "DIFFIO_RX_B75n_AA20") (pintype "bidirectional+no_connect"))
    )
    (net (code "116") (name "unconnected-(D2C-DIFFIO_RX_B75p-PadY19)") (class "Default")
      (node (ref "D2") (pin "Y19") (pinfunction "DIFFIO_RX_B75p_Y19") (pintype "bidirectional+no_connect"))
    )
    (net (code "117") (name "unconnected-(D2C-DIFFIO_RX_B78n-PadAC23)") (class "Default")
      (node (ref "D2") (pin "AC23") (pinfunction "DIFFIO_RX_B78n_AC23") (pintype "bidirectional+no_connect"))
    )
    (net (code "118") (name "unconnected-(D2C-DIFFIO_RX_B78p-PadAC22)") (class "Default")
      (node (ref "D2") (pin "AC22") (pinfunction "DIFFIO_RX_B78p_AC22") (pintype "bidirectional+no_connect"))
    )
    (net (code "119") (name "unconnected-(D2C-DIFFIO_TX_B80n-PadAE24)") (class "Default")
      (node (ref "D2") (pin "AE24") (pinfunction "DIFFIO_TX_B80n_AE24") (pintype "bidirectional+no_connect"))
    )
    (net (code "120") (name "unconnected-(D2C-DIFFIO_TX_B80p-PadAD24)") (class "Default")
      (node (ref "D2") (pin "AD24") (pinfunction "DIFFIO_TX_B80p_AD24") (pintype "bidirectional+no_connect"))
    )
    (net (code "121") (name "unconnected-(D2C-GND-PadAA19)") (class "Default")
      (node (ref "D2") (pin "AA19") (pinfunction "GND_AA19") (pintype "bidirectional"))
    )
    (net (code "122") (name "unconnected-(D2C-GND-PadAA21)") (class "Default")
      (node (ref "D2") (pin "AA21") (pinfunction "GND_AA21") (pintype "bidirectional"))
    )
    (net (code "123") (name "unconnected-(D2C-GND-PadAB21)") (class "Default")
      (node (ref "D2") (pin "AB21") (pinfunction "GND_AB21") (pintype "bidirectional"))
    )
    (net (code "124") (name "unconnected-(D2C-GND-PadAF26)") (class "Default")
      (node (ref "D2") (pin "AF26") (pinfunction "GND_AF26") (pintype "bidirectional"))
    )
    (net (code "125") (name "unconnected-(D2C-GND-PadAG26)") (class "Default")
      (node (ref "D2") (pin "AG26") (pinfunction "GND_AG26") (pintype "bidirectional"))
    )
    (net (code "126") (name "unconnected-(D2C-GND-PadAH19)") (class "Default")
      (node (ref "D2") (pin "AH19") (pinfunction "GND_AH19") (pintype "bidirectional"))
    )
    (net (code "127") (name "unconnected-(D2C-GND-PadAH22)") (class "Default")
      (node (ref "D2") (pin "AH22") (pinfunction "GND_AH22") (pintype "bidirectional"))
    )
    (net (code "128") (name "unconnected-(D2C-GND-PadAH25)") (class "Default")
      (node (ref "D2") (pin "AH25") (pinfunction "GND_AH25") (pintype "bidirectional"))
    )
    (net (code "129") (name "unconnected-(D2C-GND-PadAJ25)") (class "Default")
      (node (ref "D2") (pin "AJ25") (pinfunction "GND_AJ25") (pintype "bidirectional"))
    )
    (net (code "130") (name "unconnected-(D2C-GND-PadAJ26)") (class "Default")
      (node (ref "D2") (pin "AJ26") (pinfunction "GND_AJ26") (pintype "bidirectional"))
    )
    (net (code "131") (name "unconnected-(D2C-GND-PadAK29)") (class "Default")
      (node (ref "D2") (pin "AK29") (pinfunction "GND_AK29") (pintype "bidirectional"))
    )
    (net (code "132") (name "unconnected-(D2C-GND-PadV18)") (class "Default")
      (node (ref "D2") (pin "V18") (pinfunction "GND_V18") (pintype "bidirectional"))
    )
    (net (code "133") (name "unconnected-(D2C-GND-PadW19)") (class "Default")
      (node (ref "D2") (pin "W19") (pinfunction "GND_W19") (pintype "bidirectional"))
    )
    (net (code "134") (name "unconnected-(D2C-GND-PadY18)") (class "Default")
      (node (ref "D2") (pin "Y18") (pinfunction "GND_Y18") (pintype "bidirectional"))
    )
    (net (code "135") (name "unconnected-(D2C-IO-PadAF25)") (class "Default")
      (node (ref "D2") (pin "AF25") (pinfunction "IO_AF25") (pintype "bidirectional+no_connect"))
    )
    (net (code "136") (name "unconnected-(D2C-IO-PadAH27)") (class "Default")
      (node (ref "D2") (pin "AH27") (pinfunction "IO_AH27") (pintype "bidirectional+no_connect"))
    )
    (net (code "137") (name "unconnected-(D2C-IO-PadAJ19)") (class "Default")
      (node (ref "D2") (pin "AJ19") (pinfunction "IO_AJ19") (pintype "bidirectional+no_connect"))
    )
    (net (code "138") (name "unconnected-(D2C-IO-PadAK16)") (class "Default")
      (node (ref "D2") (pin "AK16") (pinfunction "IO_AK16") (pintype "bidirectional+no_connect"))
    )
    (net (code "139") (name "unconnected-(D2C-IO-PadAK28)") (class "Default")
      (node (ref "D2") (pin "AK28") (pinfunction "IO_AK28") (pintype "bidirectional+no_connect"))
    )
    (net (code "140") (name "unconnected-(U1C-NC-PadJ1)") (class "Default")
      (node (ref "U1") (pin "J1") (pinfunction "NC_J1") (pintype "passive"))
    )
    (net (code "141") (name "unconnected-(U1C-NC-PadJ9)") (class "Default")
      (node (ref "U1") (pin "J9") (pinfunction "NC_J9") (pintype "passive"))
    )
    (net (code "142") (name "unconnected-(U1C-NC-PadL1)") (class "Default")
      (node (ref "U1") (pin "L1") (pinfunction "NC_L1") (pintype "passive"))
    )
    (net (code "143") (name "unconnected-(U1C-NC-PadL9)") (class "Default")
      (node (ref "U1") (pin "L9") (pinfunction "NC_L9") (pintype "passive"))
    )
    (net (code "144") (name "unconnected-(U1C-NC-PadM7)") (class "Default")
      (node (ref "U1") (pin "M7") (pinfunction "NC_M7") (pintype "passive"))
    )
    (net (code "145") (name "unconnected-(U2C-NC-PadJ1)") (class "Default")
      (node (ref "U2") (pin "J1") (pinfunction "NC_J1") (pintype "passive"))
    )
    (net (code "146") (name "unconnected-(U2C-NC-PadJ9)") (class "Default")
      (node (ref "U2") (pin "J9") (pinfunction "NC_J9") (pintype "passive"))
    )
    (net (code "147") (name "unconnected-(U2C-NC-PadL1)") (class "Default")
      (node (ref "U2") (pin "L1") (pinfunction "NC_L1") (pintype "passive"))
    )
    (net (code "148") (name "unconnected-(U2C-NC-PadL9)") (class "Default")
      (node (ref "U2") (pin "L9") (pinfunction "NC_L9") (pintype "passive"))
    )
    (net (code "149") (name "unconnected-(U2C-NC-PadM7)") (class "Default")
      (node (ref "U2") (pin "M7") (pinfunction "NC_M7") (pintype "passive"))
    )
  )
)
